# S7CAS-PLEIADES-CARTE-MERE_P02_USB.net
KiCad netlist of a schematic drawn in Altium Designer
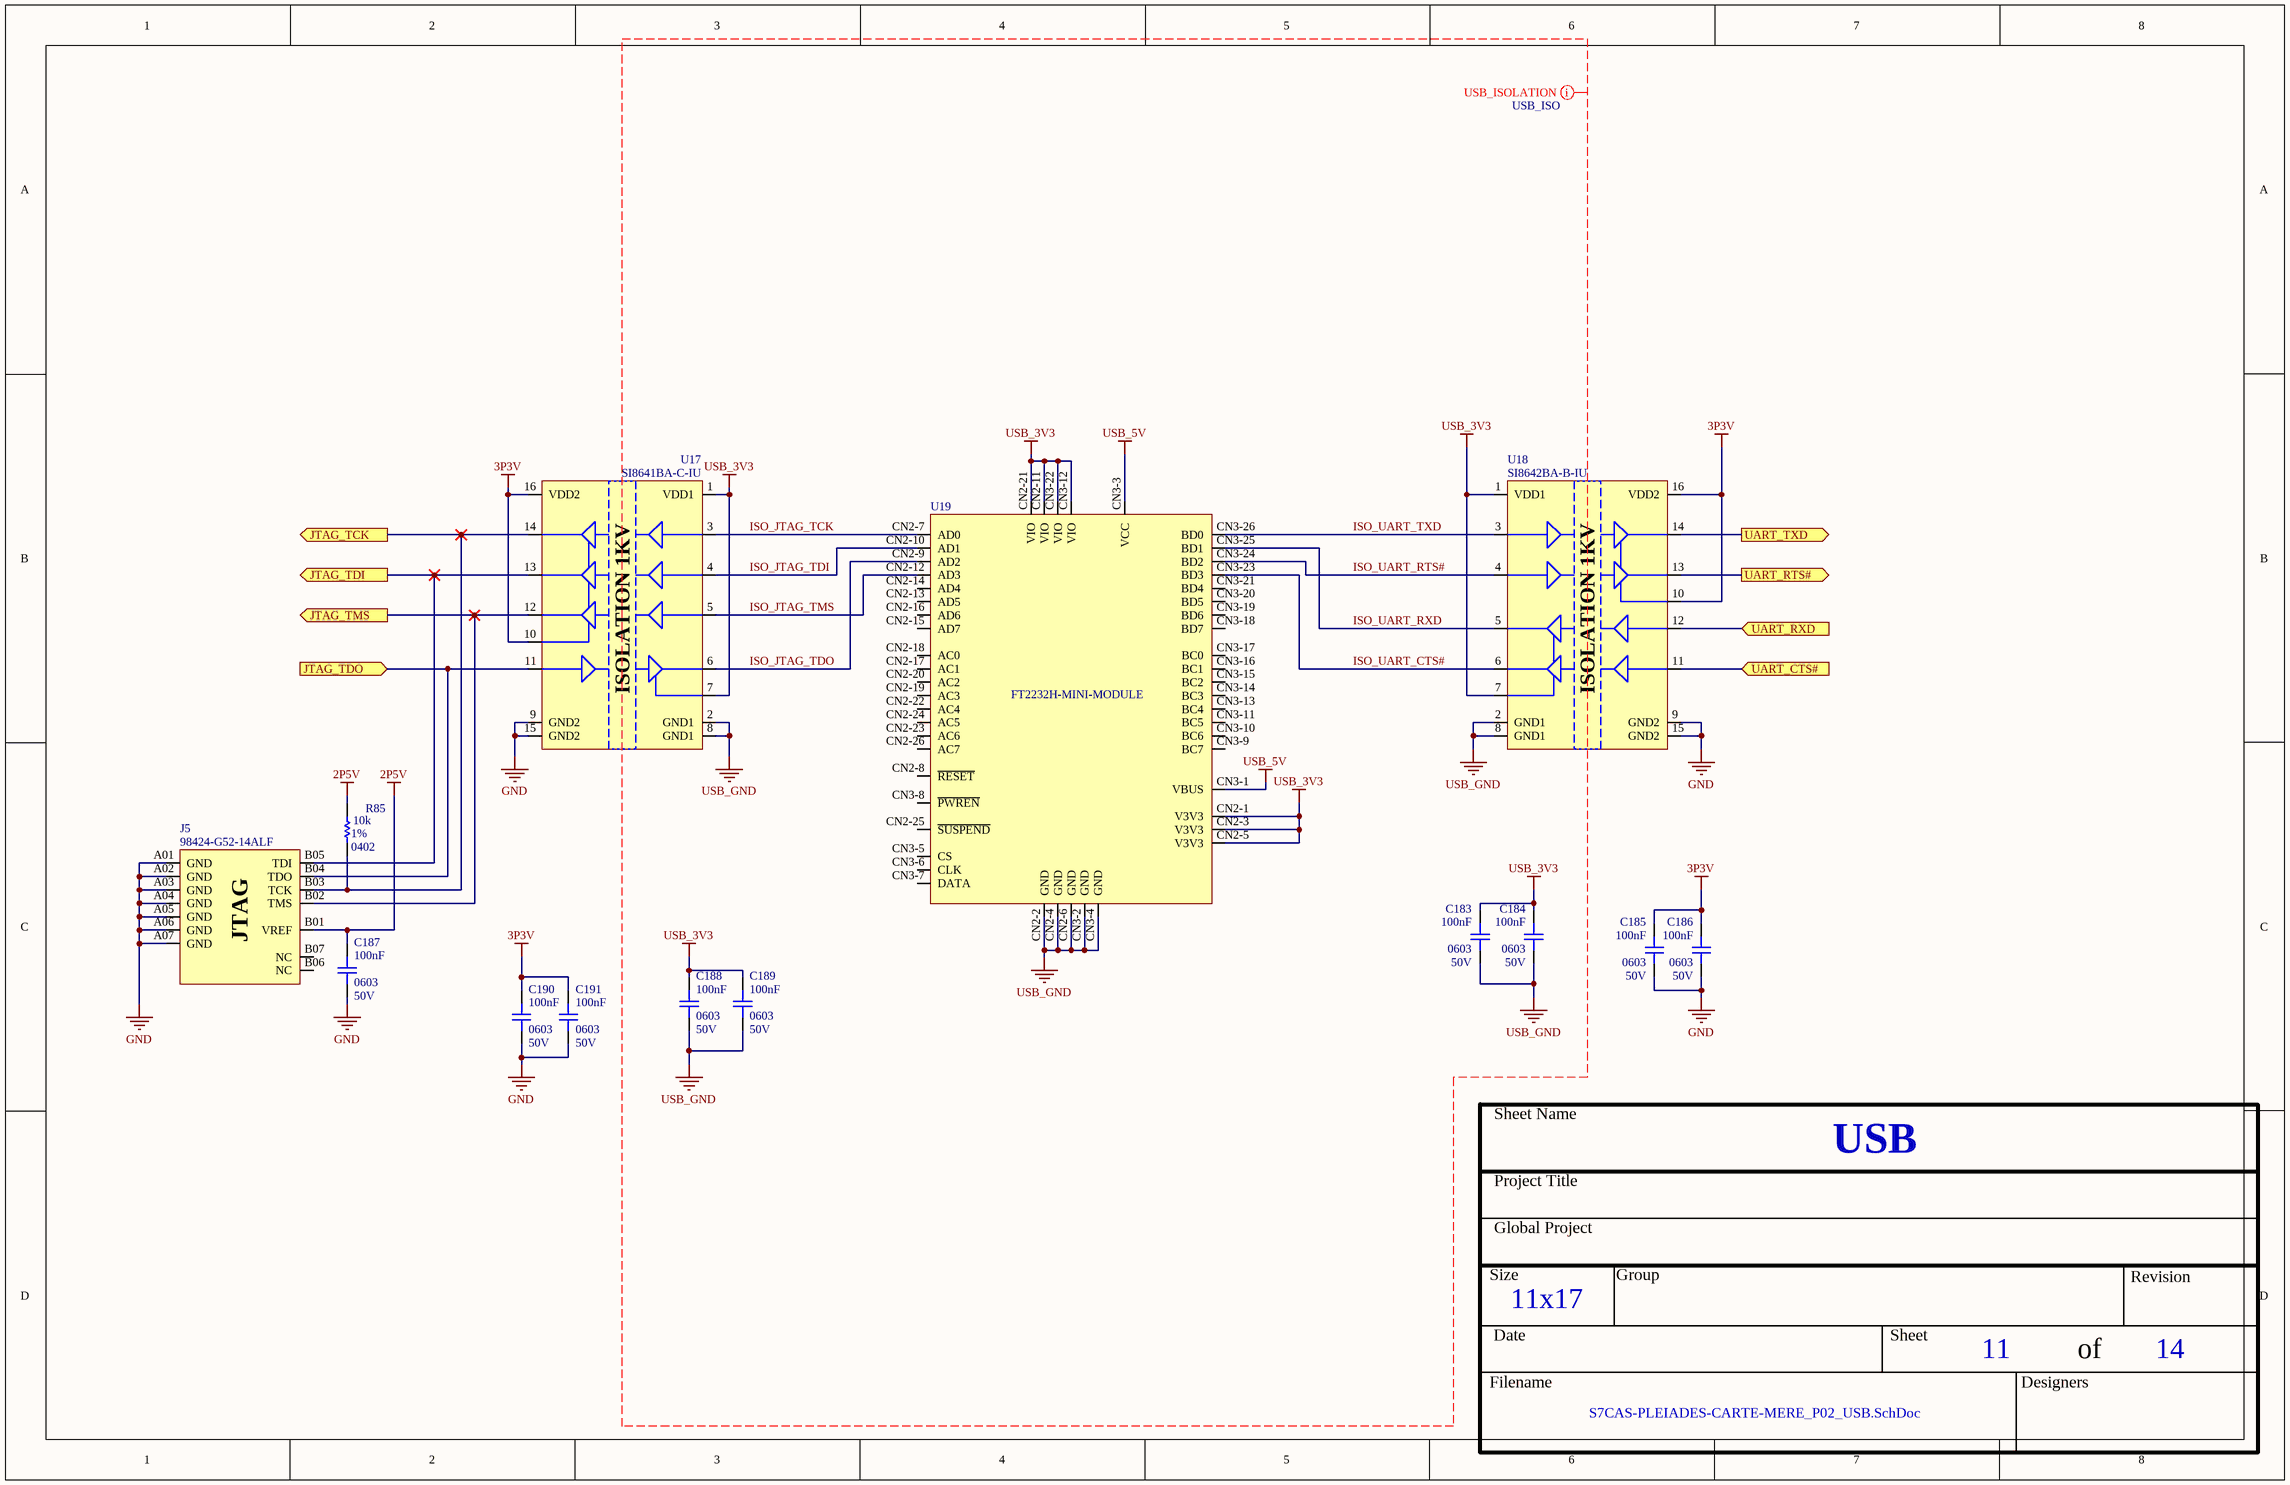
[diagram p0: S7CAS-PLEIADES-CARTE-MERE_P02_USB.SchDoc]

(export (version "E")
  (design (tool "Eeschema 10.0.6"))
  (components
    (comp (ref "C183")
      (value "100nF")
      (footprint "CAP_0603")
      (description "CAP - 0603")
      (fields
        (field (name "VOLTAGE") "50V")
        (field (name "PACKAGE") "0603")
        (field (name "CREATEDBY") "Jonathan Bouchard")
      )
      (libsource (lib "S7CAS_Lib2019_REV1_00") (part "CAP - 0603"))
    )
    (comp (ref "C184")
      (value "100nF")
      (footprint "CAP_0603")
      (description "CAP - 0603")
      (fields
        (field (name "VOLTAGE") "50V")
        (field (name "PACKAGE") "0603")
        (field (name "CREATEDBY") "Jonathan Bouchard")
      )
      (libsource (lib "S7CAS_Lib2019_REV1_00") (part "CAP - 0603"))
    )
    (comp (ref "C185")
      (value "100nF")
      (footprint "CAP_0603")
      (description "CAP - 0603")
      (fields
        (field (name "VOLTAGE") "50V")
        (field (name "PACKAGE") "0603")
        (field (name "CREATEDBY") "Jonathan Bouchard")
      )
      (libsource (lib "S7CAS_Lib2019_REV1_00") (part "CAP - 0603"))
    )
    (comp (ref "C186")
      (value "100nF")
      (footprint "CAP_0603")
      (description "CAP - 0603")
      (fields
        (field (name "VOLTAGE") "50V")
        (field (name "PACKAGE") "0603")
        (field (name "CREATEDBY") "Jonathan Bouchard")
      )
      (libsource (lib "S7CAS_Lib2019_REV1_00") (part "CAP - 0603"))
    )
    (comp (ref "C187")
      (value "100nF")
      (footprint "CAP_0603")
      (description "CAP - 0603")
      (fields
        (field (name "VOLTAGE") "50V")
        (field (name "PACKAGE") "0603")
        (field (name "CREATEDBY") "Jonathan Bouchard")
      )
      (libsource (lib "S7CAS_Lib2019_REV1_00") (part "CAP - 0603"))
    )
    (comp (ref "C188")
      (value "100nF")
      (footprint "CAP_0603")
      (description "CAP - 0603")
      (fields
        (field (name "VOLTAGE") "50V")
        (field (name "PACKAGE") "0603")
        (field (name "CREATEDBY") "Jonathan Bouchard")
      )
      (libsource (lib "S7CAS_Lib2019_REV1_00") (part "CAP - 0603"))
    )
    (comp (ref "C189")
      (value "100nF")
      (footprint "CAP_0603")
      (description "CAP - 0603")
      (fields
        (field (name "VOLTAGE") "50V")
        (field (name "PACKAGE") "0603")
        (field (name "CREATEDBY") "Jonathan Bouchard")
      )
      (libsource (lib "S7CAS_Lib2019_REV1_00") (part "CAP - 0603"))
    )
    (comp (ref "C190")
      (value "100nF")
      (footprint "CAP_0603")
      (description "CAP - 0603")
      (fields
        (field (name "VOLTAGE") "50V")
        (field (name "PACKAGE") "0603")
        (field (name "CREATEDBY") "Jonathan Bouchard")
      )
      (libsource (lib "S7CAS_Lib2019_REV1_00") (part "CAP - 0603"))
    )
    (comp (ref "C191")
      (value "100nF")
      (footprint "CAP_0603")
      (description "CAP - 0603")
      (fields
        (field (name "VOLTAGE") "50V")
        (field (name "PACKAGE") "0603")
        (field (name "CREATEDBY") "Jonathan Bouchard")
      )
      (libsource (lib "S7CAS_Lib2019_REV1_00") (part "CAP - 0603"))
    )
    (comp (ref "J5")
      (value "98424-G52-14ALF")
      (footprint "CON_JTAG_98424-G52-14ALF")
      (description "CONN -  JTAG HEADER XILINX - 14-SMD")
      (fields (field (name "MFG") "Amphenol") (field (name "CREATEDBY") "Jonathan Bouchard"))
      (libsource (lib "S7CAS_Lib2019_REV1_00") (part "CONN_JTAG_98424-G52-14ALF"))
    )
    (comp (ref "R85")
      (value "10k")
      (footprint "RES_0402")
      (description "RES - 0402")
      (fields
        (field (name "VOLTAGE") "50V")
        (field (name "POWER") "1/16W")
        (field (name "PACKAGE") "0402")
        (field (name "PRECISION") "1%")
        (field (name "CREATEDBY") "Jonathan Bouchard")
      )
      (libsource (lib "S7CAS_Lib2019_REV1_00") (part "RES - 0402"))
    )
    (comp (ref "U17")
      (value "SI8641BA-C-IU")
      (footprint "ISO_SI8642BA-B-IU")
      (description "ISO - DIGITAL ISOLATOR 1KV 4CH 3:1 GEN PURP -  SOP-16")
      (fields
        (field (name "VOLTAGE") "2.5 V ~ 5.5 V")
        (field (name "MFG") "Silicon Labs")
        (field (name "CREATEDBY") "Jonathan Bouchard")
      )
      (libsource (lib "S7CAS_Lib2019_REV1_00") (part "ISO_SI8641BA-C-IU"))
    )
    (comp (ref "U18")
      (value "SI8642BA-B-IU")
      (footprint "ISO_SI8642BA-B-IU")
      (description "ISO - DIGITAL ISOLATOR 1KV 4CH 2:2 GEN PURP -  SOP-16")
      (fields
        (field (name "VOLTAGE") "2.5 V ~ 5.5 V")
        (field (name "MFG") "Silicon Labs")
        (field (name "CREATEDBY") "Jonathan Bouchard")
      )
      (libsource (lib "S7CAS_Lib2019_REV1_00") (part "ISO_SI8642BA-B-IU"))
    )
    (comp (ref "U19")
      (value "FT2232H-MINI-MODULE")
      (footprint "COM_USB_FT2232H-MINI-MODULE")
      (description "COM - USB FTDI FT2232H Mini-Module - TH")
      (fields (field (name "MFG") "Micrel") (field (name "CREATEDBY") "Jonathan Bouchard"))
      (libsource (lib "S7CAS_Lib2019_REV1_00") (part "COM_USB_FT2232H-MINI-MODULE"))
    )
  )
  (nets
    (net (code "1") (name "/ISO_JTAG_TCK") (class "Default")
      (node (ref "U17") (pin "3") (pinfunction "A1_3") (pintype "passive"))
      (node (ref "U19") (pin "CN2-7") (pinfunction "AD0_CN2-7") (pintype "passive"))
    )
    (net (code "2") (name "/ISO_JTAG_TDI") (class "Default")
      (node (ref "U17") (pin "4") (pinfunction "A2_4") (pintype "passive"))
      (node (ref "U19") (pin "CN2-10") (pinfunction "AD1_CN2-10") (pintype "passive"))
    )
    (net (code "3") (name "/ISO_JTAG_TDO") (class "Default")
      (node (ref "U17") (pin "6") (pinfunction "A4_6") (pintype "passive"))
      (node (ref "U19") (pin "CN2-9") (pinfunction "AD2_CN2-9") (pintype "passive"))
    )
    (net (code "4") (name "/ISO_JTAG_TMS") (class "Default")
      (node (ref "U17") (pin "5") (pinfunction "A3_5") (pintype "passive"))
      (node (ref "U19") (pin "CN2-12") (pinfunction "AD3_CN2-12") (pintype "passive"))
    )
    (net (code "5") (name "/ISO_UART_CTS#") (class "Default")
      (node (ref "U18") (pin "6") (pinfunction "A4_6") (pintype "passive"))
      (node (ref "U19") (pin "CN3-23") (pinfunction "BD3_CN3-23") (pintype "passive"))
    )
    (net (code "6") (name "/ISO_UART_RTS#") (class "Default")
      (node (ref "U18") (pin "4") (pinfunction "A2_4") (pintype "passive"))
      (node (ref "U19") (pin "CN3-24") (pinfunction "BD2_CN3-24") (pintype "passive"))
    )
    (net (code "7") (name "/ISO_UART_RXD") (class "Default")
      (node (ref "U18") (pin "5") (pinfunction "A3_5") (pintype "passive"))
      (node (ref "U19") (pin "CN3-25") (pinfunction "BD1_CN3-25") (pintype "passive"))
    )
    (net (code "8") (name "/ISO_UART_TXD") (class "Default")
      (node (ref "U18") (pin "3") (pinfunction "A1_3") (pintype "passive"))
      (node (ref "U19") (pin "CN3-26") (pinfunction "BD0_CN3-26") (pintype "passive"))
    )
    (net (code "9") (name "/JTAG_TCK") (class "Default")
      (node (ref "J5") (pin "B03") (pinfunction "TCK_B03") (pintype "passive"))
      (node (ref "R85") (pin "1") (pinfunction "1_1") (pintype "passive"))
      (node (ref "U17") (pin "14") (pinfunction "B1_14") (pintype "passive"))
    )
    (net (code "10") (name "/JTAG_TDI") (class "Default")
      (node (ref "J5") (pin "B05") (pinfunction "TDI_B05") (pintype "passive"))
      (node (ref "U17") (pin "13") (pinfunction "B2_13") (pintype "passive"))
    )
    (net (code "11") (name "/JTAG_TDO") (class "Default")
      (node (ref "J5") (pin "B04") (pinfunction "TDO_B04") (pintype "passive"))
      (node (ref "U17") (pin "11") (pinfunction "B4_11") (pintype "passive"))
    )
    (net (code "12") (name "/JTAG_TMS") (class "Default")
      (node (ref "J5") (pin "B02") (pinfunction "TMS_B02") (pintype "passive"))
      (node (ref "U17") (pin "12") (pinfunction "B3_12") (pintype "passive"))
    )
    (net (code "13") (name "/UART_CTS#") (class "Default")
      (node (ref "U18") (pin "11") (pinfunction "B4_11") (pintype "passive"))
    )
    (net (code "14") (name "/UART_RTS#") (class "Default")
      (node (ref "U18") (pin "13") (pinfunction "B2_13") (pintype "passive"))
    )
    (net (code "15") (name "/UART_RXD") (class "Default")
      (node (ref "U18") (pin "12") (pinfunction "B3_12") (pintype "passive"))
    )
    (net (code "16") (name "/UART_TXD") (class "Default")
      (node (ref "U18") (pin "14") (pinfunction "B1_14") (pintype "passive"))
    )
    (net (code "17") (name "2P5V") (class "Default")
      (node (ref "C187") (pin "2") (pinfunction "2_2") (pintype "passive"))
      (node (ref "J5") (pin "B01") (pinfunction "VREF_B01") (pintype "passive"))
      (node (ref "R85") (pin "2") (pinfunction "2_2") (pintype "passive"))
    )
    (net (code "18") (name "3P3V") (class "Default")
      (node (ref "C185") (pin "2") (pinfunction "2_2") (pintype "passive"))
      (node (ref "C186") (pin "2") (pinfunction "2_2") (pintype "passive"))
      (node (ref "C190") (pin "2") (pinfunction "2_2") (pintype "passive"))
      (node (ref "C191") (pin "2") (pinfunction "2_2") (pintype "passive"))
      (node (ref "U17") (pin "10") (pinfunction "EN2_10") (pintype "passive"))
      (node (ref "U17") (pin "16") (pinfunction "VDD2_16") (pintype "power_in"))
      (node (ref "U18") (pin "10") (pinfunction "EN2_10") (pintype "passive"))
      (node (ref "U18") (pin "16") (pinfunction "VDD2_16") (pintype "power_in"))
    )
    (net (code "19") (name "GND") (class "Default")
      (node (ref "C185") (pin "1") (pinfunction "1_1") (pintype "passive"))
      (node (ref "C186") (pin "1") (pinfunction "1_1") (pintype "passive"))
      (node (ref "C187") (pin "1") (pinfunction "1_1") (pintype "passive"))
      (node (ref "C190") (pin "1") (pinfunction "1_1") (pintype "passive"))
      (node (ref "C191") (pin "1") (pinfunction "1_1") (pintype "passive"))
      (node (ref "J5") (pin "A01") (pinfunction "GND_A01") (pintype "passive"))
      (node (ref "J5") (pin "A02") (pinfunction "GND_A02") (pintype "passive"))
      (node (ref "J5") (pin "A03") (pinfunction "GND_A03") (pintype "passive"))
      (node (ref "J5") (pin "A04") (pinfunction "GND_A04") (pintype "passive"))
      (node (ref "J5") (pin "A05") (pinfunction "GND_A05") (pintype "passive"))
      (node (ref "J5") (pin "A06") (pinfunction "GND_A06") (pintype "passive"))
      (node (ref "J5") (pin "A07") (pinfunction "GND_A07") (pintype "passive"))
      (node (ref "U17") (pin "15") (pinfunction "GND2_15") (pintype "passive"))
      (node (ref "U17") (pin "9") (pinfunction "GND2_9") (pintype "passive"))
      (node (ref "U18") (pin "15") (pinfunction "GND2_15") (pintype "passive"))
      (node (ref "U18") (pin "9") (pinfunction "GND2_9") (pintype "passive"))
    )
    (net (code "20") (name "USB_3V3") (class "Default")
      (node (ref "C183") (pin "2") (pinfunction "2_2") (pintype "passive"))
      (node (ref "C184") (pin "2") (pinfunction "2_2") (pintype "passive"))
      (node (ref "C188") (pin "2") (pinfunction "2_2") (pintype "passive"))
      (node (ref "C189") (pin "2") (pinfunction "2_2") (pintype "passive"))
      (node (ref "U17") (pin "1") (pinfunction "VDD1_1") (pintype "power_in"))
      (node (ref "U17") (pin "7") (pinfunction "EN1_7") (pintype "passive"))
      (node (ref "U18") (pin "1") (pinfunction "VDD1_1") (pintype "power_in"))
      (node (ref "U18") (pin "7") (pinfunction "EN1_7") (pintype "passive"))
      (node (ref "U19") (pin "CN2-1") (pinfunction "V3V3_CN2-1") (pintype "power_in"))
      (node (ref "U19") (pin "CN2-11") (pinfunction "VIO_CN2-11") (pintype "passive"))
      (node (ref "U19") (pin "CN2-21") (pinfunction "VIO_CN2-21") (pintype "passive"))
      (node (ref "U19") (pin "CN2-3") (pinfunction "V3V3_CN2-3") (pintype "power_in"))
      (node (ref "U19") (pin "CN2-5") (pinfunction "V3V3_CN2-5") (pintype "power_in"))
      (node (ref "U19") (pin "CN3-12") (pinfunction "VIO_CN3-12") (pintype "passive"))
      (node (ref "U19") (pin "CN3-22") (pinfunction "VIO_CN3-22") (pintype "passive"))
    )
    (net (code "21") (name "USB_5V") (class "Default")
      (node (ref "U19") (pin "CN3-1") (pinfunction "VBUS_CN3-1") (pintype "passive"))
      (node (ref "U19") (pin "CN3-3") (pinfunction "VCC_CN3-3") (pintype "power_in"))
    )
    (net (code "22") (name "USB_GND") (class "Default")
      (node (ref "C183") (pin "1") (pinfunction "1_1") (pintype "passive"))
      (node (ref "C184") (pin "1") (pinfunction "1_1") (pintype "passive"))
      (node (ref "C188") (pin "1") (pinfunction "1_1") (pintype "passive"))
      (node (ref "C189") (pin "1") (pinfunction "1_1") (pintype "passive"))
      (node (ref "U17") (pin "2") (pinfunction "GND1_2") (pintype "passive"))
      (node (ref "U17") (pin "8") (pinfunction "GND1_8") (pintype "passive"))
      (node (ref "U18") (pin "2") (pinfunction "GND1_2") (pintype "passive"))
      (node (ref "U18") (pin "8") (pinfunction "GND1_8") (pintype "passive"))
      (node (ref "U19") (pin "CN2-2") (pinfunction "GND_CN2-2") (pintype "passive"))
      (node (ref "U19") (pin "CN2-4") (pinfunction "GND_CN2-4") (pintype "passive"))
      (node (ref "U19") (pin "CN2-6") (pinfunction "GND_CN2-6") (pintype "passive"))
      (node (ref "U19") (pin "CN3-2") (pinfunction "GND_CN3-2") (pintype "passive"))
      (node (ref "U19") (pin "CN3-4") (pinfunction "GND_CN3-4") (pintype "passive"))
    )
    (net (code "23") (name "unconnected-(J5-NC-PadB06)") (class "Default")
      (node (ref "J5") (pin "B06") (pinfunction "NC_B06") (pintype "passive"))
    )
    (net (code "24") (name "unconnected-(J5-NC-PadB07)") (class "Default")
      (node (ref "J5") (pin "B07") (pinfunction "NC_B07") (pintype "passive"))
    )
    (net (code "25") (name "unconnected-(U19-AC0-PadCN2-18)") (class "Default")
      (node (ref "U19") (pin "CN2-18") (pinfunction "AC0_CN2-18") (pintype "passive"))
    )
    (net (code "26") (name "unconnected-(U19-AC1-PadCN2-17)") (class "Default")
      (node (ref "U19") (pin "CN2-17") (pinfunction "AC1_CN2-17") (pintype "passive"))
    )
    (net (code "27") (name "unconnected-(U19-AC2-PadCN2-20)") (class "Default")
      (node (ref "U19") (pin "CN2-20") (pinfunction "AC2_CN2-20") (pintype "passive"))
    )
    (net (code "28") (name "unconnected-(U19-AC3-PadCN2-19)") (class "Default")
      (node (ref "U19") (pin "CN2-19") (pinfunction "AC3_CN2-19") (pintype "passive"))
    )
    (net (code "29") (name "unconnected-(U19-AC4-PadCN2-22)") (class "Default")
      (node (ref "U19") (pin "CN2-22") (pinfunction "AC4_CN2-22") (pintype "passive"))
    )
    (net (code "30") (name "unconnected-(U19-AC5-PadCN2-24)") (class "Default")
      (node (ref "U19") (pin "CN2-24") (pinfunction "AC5_CN2-24") (pintype "passive"))
    )
    (net (code "31") (name "unconnected-(U19-AC6-PadCN2-23)") (class "Default")
      (node (ref "U19") (pin "CN2-23") (pinfunction "AC6_CN2-23") (pintype "passive"))
    )
    (net (code "32") (name "unconnected-(U19-AC7-PadCN2-26)") (class "Default")
      (node (ref "U19") (pin "CN2-26") (pinfunction "AC7_CN2-26") (pintype "passive"))
    )
    (net (code "33") (name "unconnected-(U19-AD4-PadCN2-14)") (class "Default")
      (node (ref "U19") (pin "CN2-14") (pinfunction "AD4_CN2-14") (pintype "passive"))
    )
    (net (code "34") (name "unconnected-(U19-AD5-PadCN2-13)") (class "Default")
      (node (ref "U19") (pin "CN2-13") (pinfunction "AD5_CN2-13") (pintype "passive"))
    )
    (net (code "35") (name "unconnected-(U19-AD6-PadCN2-16)") (class "Default")
      (node (ref "U19") (pin "CN2-16") (pinfunction "AD6_CN2-16") (pintype "passive"))
    )
    (net (code "36") (name "unconnected-(U19-AD7-PadCN2-15)") (class "Default")
      (node (ref "U19") (pin "CN2-15") (pinfunction "AD7_CN2-15") (pintype "passive"))
    )
    (net (code "37") (name "unconnected-(U19-BC0-PadCN3-17)") (class "Default")
      (node (ref "U19") (pin "CN3-17") (pinfunction "BC0_CN3-17") (pintype "passive"))
    )
    (net (code "38") (name "unconnected-(U19-BC1-PadCN3-16)") (class "Default")
      (node (ref "U19") (pin "CN3-16") (pinfunction "BC1_CN3-16") (pintype "passive"))
    )
    (net (code "39") (name "unconnected-(U19-BC2-PadCN3-15)") (class "Default")
      (node (ref "U19") (pin "CN3-15") (pinfunction "BC2_CN3-15") (pintype "passive"))
    )
    (net (code "40") (name "unconnected-(U19-BC3-PadCN3-14)") (class "Default")
      (node (ref "U19") (pin "CN3-14") (pinfunction "BC3_CN3-14") (pintype "passive"))
    )
    (net (code "41") (name "unconnected-(U19-BC4-PadCN3-13)") (class "Default")
      (node (ref "U19") (pin "CN3-13") (pinfunction "BC4_CN3-13") (pintype "passive"))
    )
    (net (code "42") (name "unconnected-(U19-BC5-PadCN3-11)") (class "Default")
      (node (ref "U19") (pin "CN3-11") (pinfunction "BC5_CN3-11") (pintype "passive"))
    )
    (net (code "43") (name "unconnected-(U19-BC6-PadCN3-10)") (class "Default")
      (node (ref "U19") (pin "CN3-10") (pinfunction "BC6_CN3-10") (pintype "passive"))
    )
    (net (code "44") (name "unconnected-(U19-BC7-PadCN3-9)") (class "Default")
      (node (ref "U19") (pin "CN3-9") (pinfunction "BC7_CN3-9") (pintype "passive"))
    )
    (net (code "45") (name "unconnected-(U19-BD4-PadCN3-21)") (class "Default")
      (node (ref "U19") (pin "CN3-21") (pinfunction "BD4_CN3-21") (pintype "passive"))
    )
    (net (code "46") (name "unconnected-(U19-BD5-PadCN3-20)") (class "Default")
      (node (ref "U19") (pin "CN3-20") (pinfunction "BD5_CN3-20") (pintype "passive"))
    )
    (net (code "47") (name "unconnected-(U19-BD6-PadCN3-19)") (class "Default")
      (node (ref "U19") (pin "CN3-19") (pinfunction "BD6_CN3-19") (pintype "passive"))
    )
    (net (code "48") (name "unconnected-(U19-BD7-PadCN3-18)") (class "Default")
      (node (ref "U19") (pin "CN3-18") (pinfunction "BD7_CN3-18") (pintype "passive"))
    )
    (net (code "49") (name "unconnected-(U19-CLK-PadCN3-6)") (class "Default")
      (node (ref "U19") (pin "CN3-6") (pinfunction "CLK_CN3-6") (pintype "passive"))
    )
    (net (code "50") (name "unconnected-(U19-CS-PadCN3-5)") (class "Default")
      (node (ref "U19") (pin "CN3-5") (pinfunction "CS_CN3-5") (pintype "passive"))
    )
    (net (code "51") (name "unconnected-(U19-DATA-PadCN3-7)") (class "Default")
      (node (ref "U19") (pin "CN3-7") (pinfunction "DATA_CN3-7") (pintype "passive"))
    )
    (net (code "52") (name "unconnected-(U19-PWREN-PadCN3-8)") (class "Default")
      (node (ref "U19") (pin "CN3-8") (pinfunction "PWREN_CN3-8") (pintype "passive"))
    )
    (net (code "53") (name "unconnected-(U19-RESET-PadCN2-8)") (class "Default")
      (node (ref "U19") (pin "CN2-8") (pinfunction "RESET_CN2-8") (pintype "passive"))
    )
    (net (code "54") (name "unconnected-(U19-SUSPEND-PadCN2-25)") (class "Default")
      (node (ref "U19") (pin "CN2-25") (pinfunction "SUSPEND_CN2-25") (pintype "passive"))
    )
  )
)
